# SO8_Breakout_Board.net
KiCad netlist of a schematic drawn in EAGLE
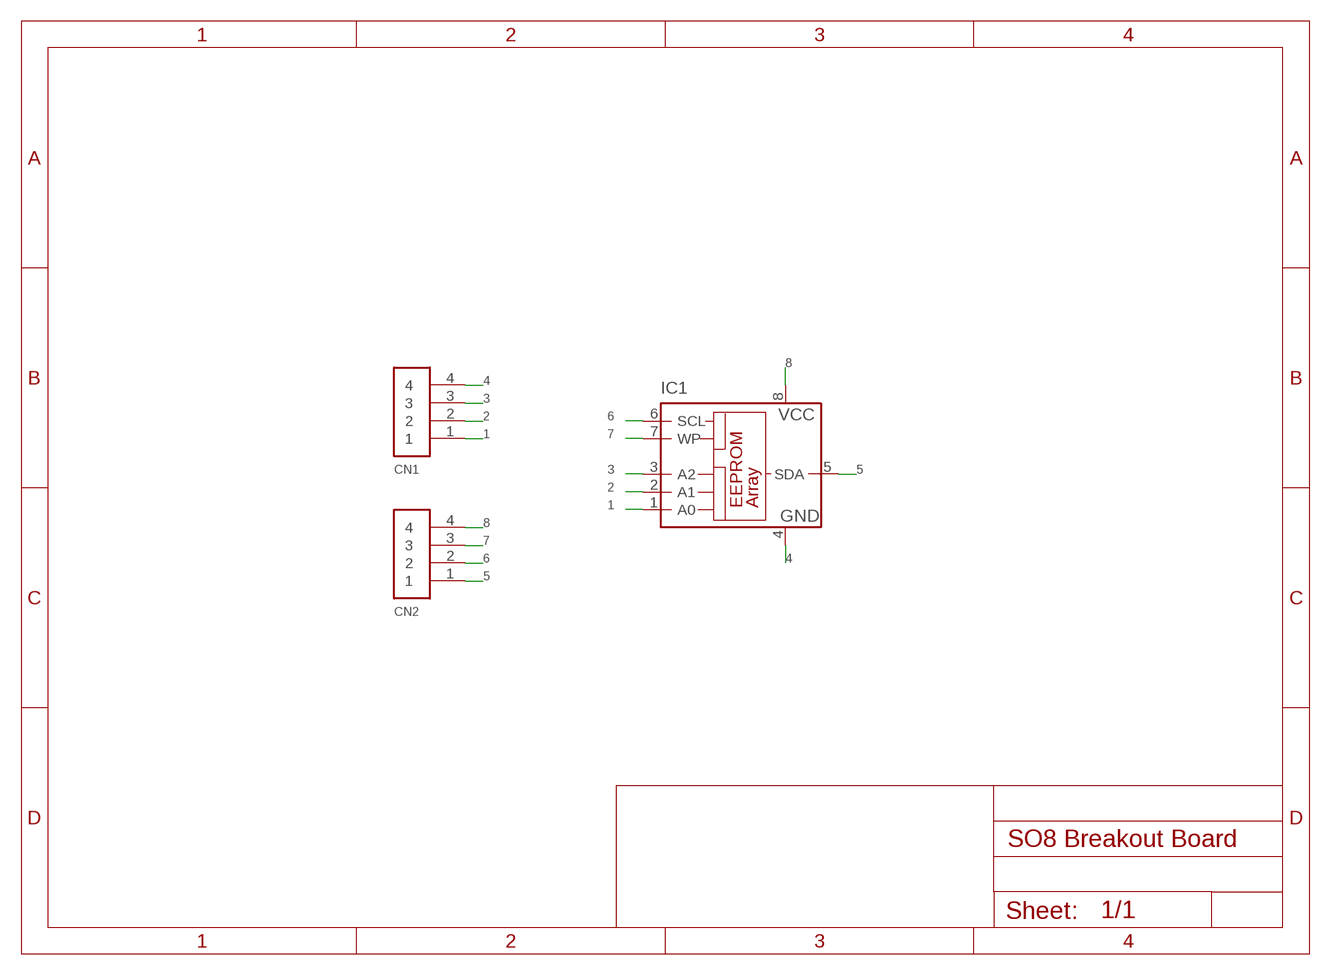
[diagram p0: schematic, sheet 1]

(export (version "E")
  (design (tool "Eeschema 10.0.6"))
  (components
    (comp (ref "CN1")
      (value "1X4-BIG")
      (footprint "eagle-import:1X04-BIG")
      (libsource (lib "eagle-import") (part "1X4-BIG"))
    )
    (comp (ref "CN2")
      (value "1X4-BIG")
      (footprint "eagle-import:1X04-BIG")
      (libsource (lib "eagle-import") (part "1X4-BIG"))
    )
    (comp (ref "IC1")
      (value "24AA01SN")
      (footprint "eagle-import:SO-08")
      (fields (field (name "MF") "MICROCHIP") (field (name "MPN") "24AA01/SN"))
      (libsource (lib "eagle-import") (part "24SNAA01"))
    )
  )
  (nets
    (net (code "1") (name "/1") (class "Default")
      (node (ref "CN1") (pin "1") (pinfunction "1_1") (pintype "bidirectional"))
      (node (ref "IC1") (pin "1") (pinfunction "A0_1") (pintype "input"))
    )
    (net (code "2") (name "/2") (class "Default")
      (node (ref "CN1") (pin "2") (pinfunction "2_2") (pintype "bidirectional"))
      (node (ref "IC1") (pin "2") (pinfunction "A1_2") (pintype "input"))
    )
    (net (code "3") (name "/3") (class "Default")
      (node (ref "CN1") (pin "3") (pinfunction "3_3") (pintype "bidirectional"))
      (node (ref "IC1") (pin "3") (pinfunction "A2_3") (pintype "input"))
    )
    (net (code "4") (name "/4") (class "Default")
      (node (ref "CN1") (pin "4") (pinfunction "4_4") (pintype "bidirectional"))
      (node (ref "IC1") (pin "4") (pinfunction "GND_4") (pintype "power_in"))
    )
    (net (code "5") (name "/5") (class "Default")
      (node (ref "CN2") (pin "1") (pinfunction "1_1") (pintype "bidirectional"))
      (node (ref "IC1") (pin "5") (pinfunction "SDA_5") (pintype "bidirectional"))
    )
    (net (code "6") (name "/6") (class "Default")
      (node (ref "CN2") (pin "2") (pinfunction "2_2") (pintype "bidirectional"))
      (node (ref "IC1") (pin "6") (pinfunction "SCL_6") (pintype "input"))
    )
    (net (code "7") (name "/7") (class "Default")
      (node (ref "CN2") (pin "3") (pinfunction "3_3") (pintype "bidirectional"))
      (node (ref "IC1") (pin "7") (pinfunction "WP_7") (pintype "input"))
    )
    (net (code "8") (name "/8") (class "Default")
      (node (ref "CN2") (pin "4") (pinfunction "4_4") (pintype "bidirectional"))
      (node (ref "IC1") (pin "8") (pinfunction "VCC_8") (pintype "power_in"))
    )
  )
)
